# Sheet1.net
KiCad netlist of a schematic drawn in Altium Designer
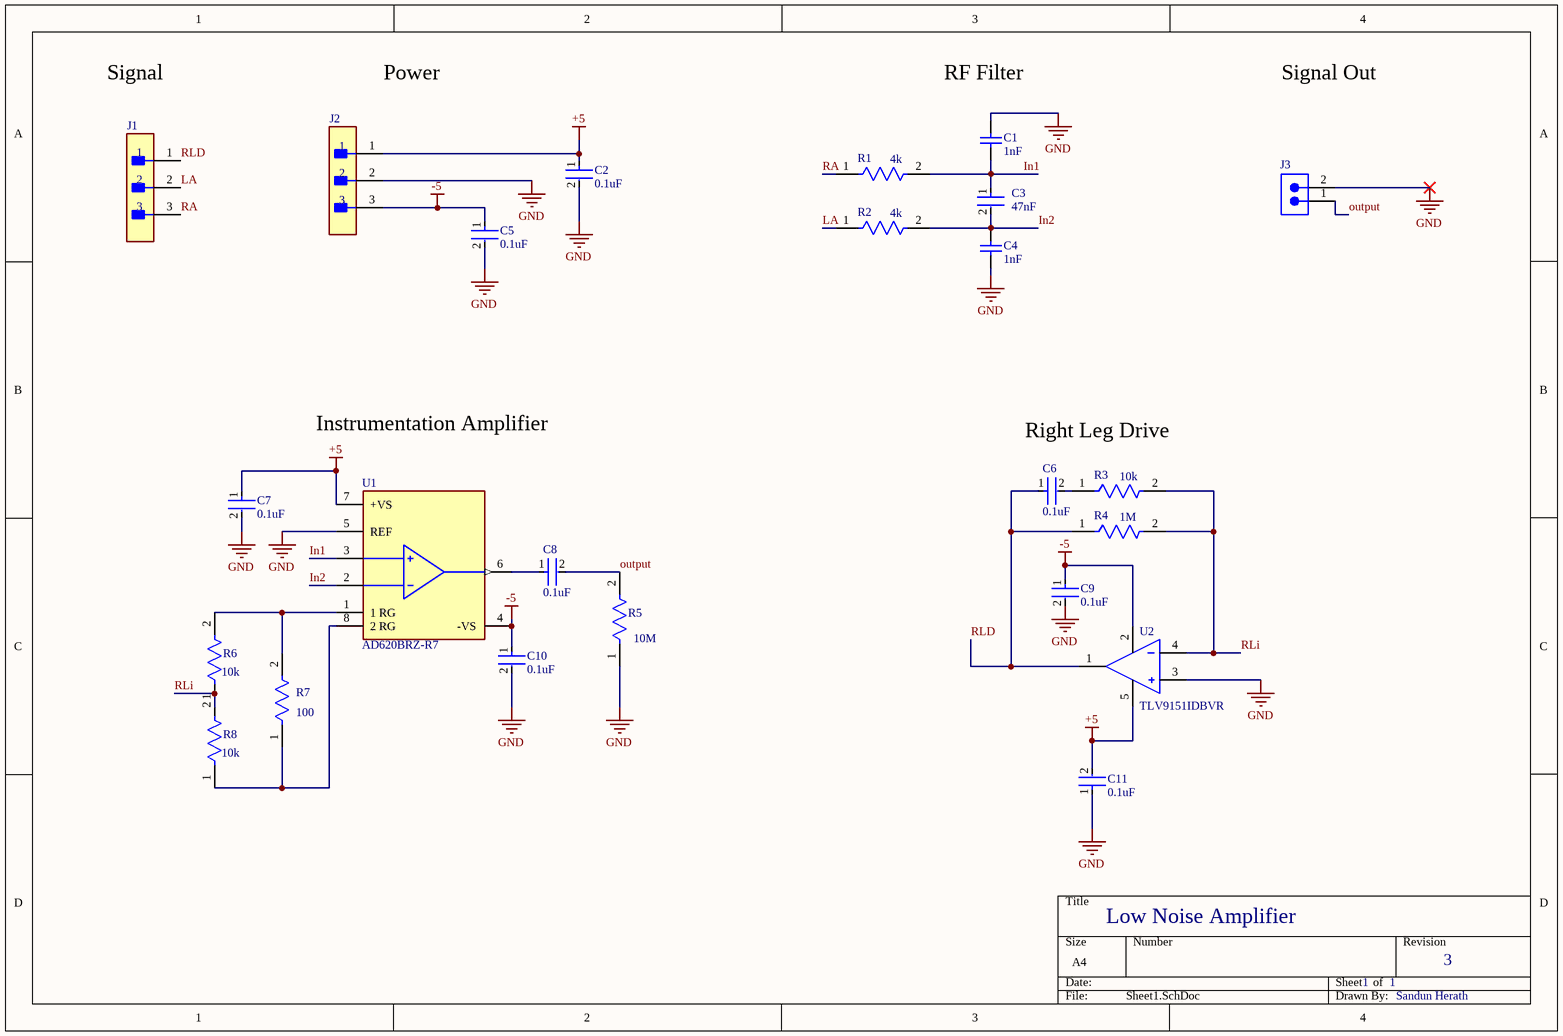
[diagram p0: Sheet1.SchDoc]

(export (version "E")
  (design (tool "Eeschema 10.0.6"))
  (components
    (comp (ref "C1")
      (value "1nF")
      (footprint "CAPC0805(2012)145_L")
      (description "CAP 1nF 50V ±5% 0805 (2012 Metric) Thickness 1.45mm SMD")
      (fields (field (name "TOLERANCE") "Â±5%"))
      (libsource (lib "Altium Content Vault") (part "CAP"))
    )
    (comp (ref "C2")
      (value "0.1uF")
      (footprint "FP-CL21-IPC_A")
      (description "CL21 Series 0805 100nF 25V ±20% Tolerance X7R Multilayer Ceramic Chip Capacitor, CL21B104MACNNNC")
      (fields (field (name "TOLERANCE") "20%"))
      (libsource (lib "Altium Content Vault") (part "b4654b650e69147ec39a6b967a45e02"))
    )
    (comp (ref "C3")
      (value "47nF")
      (footprint "FP-GRM21B-0_1-IPC_C")
      (fields (field (name "TOLERANCE") "5%"))
      (libsource (lib "Altium Content Vault") (part "b4654b650e69147ec39a6b967a45e02"))
    )
    (comp (ref "C4")
      (value "1nF")
      (footprint "CAPC0805(2012)145_L")
      (description "CAP 1nF 50V ±5% 0805 (2012 Metric) Thickness 1.45mm SMD")
      (fields (field (name "TOLERANCE") "Â±5%"))
      (libsource (lib "Altium Content Vault") (part "CAP"))
    )
    (comp (ref "C5")
      (value "0.1uF")
      (footprint "FP-CL21-IPC_A")
      (description "CL21 Series 0805 100nF 25V ±20% Tolerance X7R Multilayer Ceramic Chip Capacitor, CL21B104MACNNNC")
      (fields (field (name "TOLERANCE") "20%"))
      (libsource (lib "Altium Content Vault") (part "b4654b650e69147ec39a6b967a45e02"))
    )
    (comp (ref "C6")
      (value "0.1uF")
      (footprint "FP-CL21-IPC_A")
      (description "CL21 Series 0805 100nF 25V ±20% Tolerance X7R Multilayer Ceramic Chip Capacitor, CL21B104MACNNNC")
      (fields (field (name "TOLERANCE") "20%"))
      (libsource (lib "Altium Content Vault") (part "b4654b650e69147ec39a6b967a45e02"))
    )
    (comp (ref "C7")
      (value "0.1uF")
      (footprint "FP-CL21-IPC_A")
      (description "CL21 Series 0805 100nF 25V ±20% Tolerance X7R Multilayer Ceramic Chip Capacitor")
      (fields (field (name "TOLERANCE") "20%"))
      (libsource (lib "Altium Content Vault") (part "b4654b650e69147ec39a6b967a45e02"))
    )
    (comp (ref "C8")
      (value "0.1uF")
      (footprint "FP-CL21-IPC_A")
      (description "CL21 Series 0805 100nF 25V ±20% Tolerance X7R Multilayer Ceramic Chip Capacitor, CL21B104MACNNNC")
      (fields (field (name "TOLERANCE") "20%"))
      (libsource (lib "Altium Content Vault") (part "b4654b650e69147ec39a6b967a45e02"))
    )
    (comp (ref "C9")
      (value "0.1uF")
      (footprint "FP-CL21-IPC_A")
      (description "CL21 Series 0805 100nF 25V ±20% Tolerance X7R Multilayer Ceramic Chip Capacitor, CL21B104MACNNNC")
      (fields (field (name "TOLERANCE") "20%"))
      (libsource (lib "Altium Content Vault") (part "b4654b650e69147ec39a6b967a45e02"))
    )
    (comp (ref "C10")
      (value "0.1uF")
      (footprint "FP-CL21-IPC_A")
      (description "CL21 Series 0805 100nF 25V ±20% Tolerance X7R Multilayer Ceramic Chip Capacitor")
      (fields (field (name "TOLERANCE") "20%"))
      (libsource (lib "Altium Content Vault") (part "b4654b650e69147ec39a6b967a45e02"))
    )
    (comp (ref "C11")
      (value "0.1uF")
      (footprint "FP-CL21-IPC_A")
      (description "CL21 Series 0805 100nF 25V ±20% Tolerance X7R Multilayer Ceramic Chip Capacitor, CL21B104MACNNNC")
      (fields (field (name "TOLERANCE") "20%"))
      (libsource (lib "Altium Content Vault") (part "b4654b650e69147ec39a6b967a45e02"))
    )
    (comp (ref "J1")
      (value "B3B-XH-A(LF)(SN)")
      (footprint "FP-B3B-XH-A_LF_SN-MFG")
      (description "CONN HEADER VERT 3POS 2.5MM")
      (libsource (lib "Altium Content Vault") (part "0d3f023dd272f625e17a2be33dea85f"))
    )
    (comp (ref "J2")
      (value "B3B-XH-A(LF)(SN)")
      (footprint "FP-B3B-XH-A_LF_SN-MFG")
      (description "CONN HEADER VERT 3POS 2.5MM")
      (libsource (lib "Altium Content Vault") (part "0d3f023dd272f625e17a2be33dea85f"))
    )
    (comp (ref "J3")
      (value "61300211121")
      (footprint "61300211121")
      (libsource (lib "Altium Content Vault") (part "Header_Male_1R_02P"))
    )
    (comp (ref "R1")
      (value "4k")
      (footprint "FP-ERA6A-IPC_C")
      (description "RES 1K OHM 0.1% 1/8W 0805,  ERA6AEB102V")
      (fields (field (name "TOLERANCE") "0.1%"))
      (libsource (lib "Altium Content Vault") (part "1029c3af85768c4190bb7ad29bc67b5"))
    )
    (comp (ref "R2")
      (value "4k")
      (footprint "FP-ERA6A-IPC_C")
      (description "RES 1K OHM 0.1% 1/8W 0805,  ERA6AEB102V")
      (fields (field (name "TOLERANCE") "0.1%"))
      (libsource (lib "Altium Content Vault") (part "1029c3af85768c4190bb7ad29bc67b5"))
    )
    (comp (ref "R3")
      (value "10k")
      (footprint "FP-ERA6A-IPC_C")
      (description "RES 1K OHM 0.1% 1/8W 0805,   ERA6AEB102V")
      (fields (field (name "TOLERANCE") "0.1%"))
      (libsource (lib "Altium Content Vault") (part "1029c3af85768c4190bb7ad29bc67b5"))
    )
    (comp (ref "R4")
      (value "1M")
      (footprint "FP-ERA6A-IPC_C")
      (description "RES 1K OHM 0.1% 1/8W 0805,  ERA6AEB102V")
      (fields (field (name "TOLERANCE") "0.1%"))
      (libsource (lib "Altium Content Vault") (part "1029c3af85768c4190bb7ad29bc67b5"))
    )
    (comp (ref "R5")
      (value "10M")
      (footprint "FP-ERA6A-IPC_C")
      (description "RES 1K OHM 0.1% 1/8W 0805,  ERA6AEB102V")
      (fields (field (name "TOLERANCE") "0.1%"))
      (libsource (lib "Altium Content Vault") (part "1029c3af85768c4190bb7ad29bc67b5"))
    )
    (comp (ref "R6")
      (value "10k")
      (footprint "FP-ERA6A-IPC_C")
      (description "RES 1K OHM 0.1% 1/8W 0805,    ERA6AEB102V")
      (fields (field (name "TOLERANCE") "0.1%"))
      (libsource (lib "Altium Content Vault") (part "1029c3af85768c4190bb7ad29bc67b5"))
    )
    (comp (ref "R7")
      (value "100")
      (footprint "FP-ERA6A-IPC_C")
      (description "RES 1K OHM 0.1% 1/8W 0805,  ERA6AEB102V")
      (fields (field (name "TOLERANCE") "0.1%"))
      (libsource (lib "Altium Content Vault") (part "1029c3af85768c4190bb7ad29bc67b5"))
    )
    (comp (ref "R8")
      (value "10k")
      (footprint "FP-ERA6A-IPC_C")
      (description "RES 1K OHM 0.1% 1/8W 0805,  ERA6AEB102V")
      (fields (field (name "TOLERANCE") "0.1%"))
      (libsource (lib "Altium Content Vault") (part "1029c3af85768c4190bb7ad29bc67b5"))
    )
    (comp (ref "U1")
      (value "AD620BRZ-R7")
      (footprint "FP-R-8-IPC_C")
      (description "IC INST AMP 1 CIRCUIT 8SOIC")
      (libsource (lib "Altium Content Vault") (part "34122d4f8c853147fd0c9ba0f33876e"))
    )
    (comp (ref "U2")
      (value "TLV9151IDBVR")
      (footprint "FP-DBV0005A-IPC_A")
      (description "OPAMP")
      (libsource (lib "Altium Content Vault") (part "bdbec92199ce4306a818faf70a0ce6e"))
    )
  )
  (nets
    (net (code "1") (name "+5") (class "Default")
      (node (ref "C11") (pin "2") (pinfunction "2_2") (pintype "passive"))
      (node (ref "C2") (pin "1") (pinfunction "1_1") (pintype "passive"))
      (node (ref "C7") (pin "1") (pinfunction "1_1") (pintype "passive"))
      (node (ref "J2") (pin "1") (pinfunction "1_1") (pintype "passive"))
      (node (ref "U1") (pin "7") (pinfunction "+VS_7") (pintype "power_in"))
      (node (ref "U2") (pin "5") (pinfunction "V+_5") (pintype "power_in"))
    )
    (net (code "2") (name "-5") (class "Default")
      (node (ref "C10") (pin "1") (pinfunction "1_1") (pintype "passive"))
      (node (ref "C5") (pin "1") (pinfunction "1_1") (pintype "passive"))
      (node (ref "C9") (pin "1") (pinfunction "1_1") (pintype "passive"))
      (node (ref "J2") (pin "3") (pinfunction "3_3") (pintype "passive"))
      (node (ref "U1") (pin "4") (pinfunction "-VS_4") (pintype "power_in"))
      (node (ref "U2") (pin "2") (pinfunction "V-_2") (pintype "power_in"))
    )
    (net (code "3") (name "/In1") (class "Default")
      (node (ref "C1") (pin "1") (pinfunction "1_1") (pintype "passive"))
      (node (ref "C3") (pin "1") (pinfunction "1_1") (pintype "passive"))
      (node (ref "R1") (pin "2") (pinfunction "2_2") (pintype "passive"))
      (node (ref "U1") (pin "3") (pinfunction "+IN_3") (pintype "tri_state"))
    )
    (net (code "4") (name "/In2") (class "Default")
      (node (ref "C3") (pin "2") (pinfunction "2_2") (pintype "passive"))
      (node (ref "C4") (pin "2") (pinfunction "2_2") (pintype "passive"))
      (node (ref "R2") (pin "2") (pinfunction "2_2") (pintype "passive"))
      (node (ref "U1") (pin "2") (pinfunction "-IN_2") (pintype "tri_state"))
    )
    (net (code "5") (name "/LA") (class "Default")
      (node (ref "J1") (pin "2") (pinfunction "2_2") (pintype "passive"))
      (node (ref "R2") (pin "1") (pinfunction "1_1") (pintype "passive"))
    )
    (net (code "6") (name "/RA") (class "Default")
      (node (ref "J1") (pin "3") (pinfunction "3_3") (pintype "passive"))
      (node (ref "R1") (pin "1") (pinfunction "1_1") (pintype "passive"))
    )
    (net (code "7") (name "/RLD") (class "Default")
      (node (ref "C6") (pin "1") (pinfunction "1_1") (pintype "passive"))
      (node (ref "J1") (pin "1") (pinfunction "1_1") (pintype "passive"))
      (node (ref "R4") (pin "1") (pinfunction "1_1") (pintype "passive"))
      (node (ref "U2") (pin "1") (pinfunction "OUT_1") (pintype "passive"))
    )
    (net (code "8") (name "/RLi") (class "Default")
      (node (ref "R3") (pin "2") (pinfunction "2_2") (pintype "passive"))
      (node (ref "R4") (pin "2") (pinfunction "2_2") (pintype "passive"))
      (node (ref "R6") (pin "1") (pinfunction "1_1") (pintype "passive"))
      (node (ref "R8") (pin "2") (pinfunction "2_2") (pintype "passive"))
      (node (ref "U2") (pin "4") (pinfunction "IN-_4") (pintype "tri_state"))
    )
    (net (code "9") (name "/output") (class "Default")
      (node (ref "C8") (pin "2") (pinfunction "2_2") (pintype "passive"))
      (node (ref "J3") (pin "1") (pinfunction "1_1") (pintype "passive"))
      (node (ref "R5") (pin "2") (pinfunction "2_2") (pintype "passive"))
    )
    (net (code "10") (name "GND") (class "Default")
      (node (ref "C1") (pin "2") (pinfunction "2_2") (pintype "passive"))
      (node (ref "C10") (pin "2") (pinfunction "2_2") (pintype "passive"))
      (node (ref "C11") (pin "1") (pinfunction "1_1") (pintype "passive"))
      (node (ref "C2") (pin "2") (pinfunction "2_2") (pintype "passive"))
      (node (ref "C4") (pin "1") (pinfunction "1_1") (pintype "passive"))
      (node (ref "C5") (pin "2") (pinfunction "2_2") (pintype "passive"))
      (node (ref "C7") (pin "2") (pinfunction "2_2") (pintype "passive"))
      (node (ref "C9") (pin "2") (pinfunction "2_2") (pintype "passive"))
      (node (ref "J2") (pin "2") (pinfunction "2_2") (pintype "passive"))
      (node (ref "J3") (pin "2") (pinfunction "2_2") (pintype "passive"))
      (node (ref "R5") (pin "1") (pinfunction "1_1") (pintype "passive"))
      (node (ref "U1") (pin "5") (pinfunction "REF_5") (pintype "passive"))
      (node (ref "U2") (pin "3") (pinfunction "IN+_3") (pintype "tri_state"))
    )
    (net (code "11") (name "Net-(C6-Pad2)") (class "Default")
      (node (ref "C6") (pin "2") (pinfunction "2_2") (pintype "passive"))
      (node (ref "R3") (pin "1") (pinfunction "1_1") (pintype "passive"))
    )
    (net (code "12") (name "Net-(U1-1_RG)") (class "Default")
      (node (ref "R6") (pin "2") (pinfunction "2_2") (pintype "passive"))
      (node (ref "R7") (pin "2") (pinfunction "2_2") (pintype "passive"))
      (node (ref "U1") (pin "1") (pinfunction "1_RG_1") (pintype "passive"))
    )
    (net (code "13") (name "Net-(U1-2_RG)") (class "Default")
      (node (ref "R7") (pin "1") (pinfunction "1_1") (pintype "passive"))
      (node (ref "R8") (pin "1") (pinfunction "1_1") (pintype "passive"))
      (node (ref "U1") (pin "8") (pinfunction "2_RG_8") (pintype "passive"))
    )
    (net (code "14") (name "Net-(U1-OUTPUT)") (class "Default")
      (node (ref "C8") (pin "1") (pinfunction "1_1") (pintype "passive"))
      (node (ref "U1") (pin "6") (pinfunction "OUTPUT_6") (pintype "output"))
    )
  )
)
